# CAN_TJA1050.net
KiCad netlist of a schematic drawn in Altium Designer
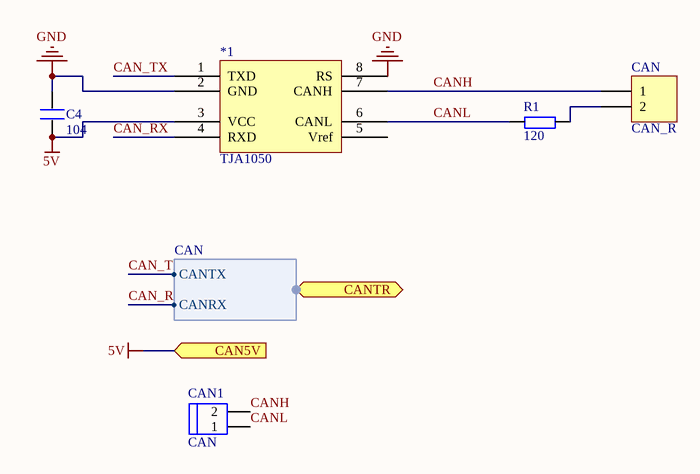
[diagram p0: CAN_TJA1050.SchDoc]

(export (version "E")
  (design (tool "Eeschema 10.0.6"))
  (components
    (comp (ref "*1") (value "TJA1050") (footprint "SOP8") (libsource (lib "TJA1050") (part "TJA1050")))
    (comp (ref "C4") (value "104") (footprint "0603P") (libsource (lib "MiniSTM32 V3.0封装库") (part "C")))
    (comp (ref "CAN")
      (value "CAN_R")
      (footprint "HDR1X2")
      (description "Header, 2-Pin")
      (fields (field (name "PUBLISHER") "Altium Limited"))
      (libsource (lib "MiniSTM32 V3.0封装库") (part "Header 2"))
    )
    (comp (ref "CAN1")
      (value "CAN")
      (footprint "HEAD2L-0.8")
      (libsource (lib "阿波罗STM32F4&F7底板封装库") (part "HEAD2"))
    )
    (comp (ref "R1") (value "120") (footprint "0603P") (libsource (lib "MiniSTM32 V3.0封装库") (part "R")))
  )
  (nets
    (net (code "2") (name "/CANH") (class "Default")
      (node (ref "*1") (pin "7") (pinfunction "CANH_7") (pintype "passive"))
      (node (ref "CAN") (pin "1") (pinfunction "1_1") (pintype "passive"))
      (node (ref "CAN1") (pin "2") (pinfunction "2_2") (pintype "passive"))
    )
    (net (code "3") (name "/CANL") (class "Default")
      (node (ref "*1") (pin "6") (pinfunction "CANL_6") (pintype "passive"))
      (node (ref "CAN1") (pin "1") (pinfunction "1_1") (pintype "passive"))
      (node (ref "R1") (pin "1") (pintype "passive"))
    )
    (net (code "4") (name "/CAN_RX") (class "Default")
      (node (ref "*1") (pin "4") (pinfunction "RXD_4") (pintype "passive"))
    )
    (net (code "5") (name "/CAN_TX") (class "Default")
      (node (ref "*1") (pin "1") (pinfunction "TXD_1") (pintype "passive"))
    )
    (net (code "7") (name "5V") (class "Default")
      (node (ref "*1") (pin "3") (pinfunction "VCC_3") (pintype "passive"))
      (node (ref "C4") (pin "1") (pintype "passive"))
    )
    (net (code "8") (name "GND") (class "Default")
      (node (ref "*1") (pin "2") (pinfunction "GND_2") (pintype "passive"))
      (node (ref "*1") (pin "8") (pinfunction "RS_8") (pintype "passive"))
      (node (ref "C4") (pin "2") (pintype "passive"))
    )
    (net (code "9") (name "Net-(CAN-Pad2)") (class "Default")
      (node (ref "CAN") (pin "2") (pinfunction "2_2") (pintype "passive"))
      (node (ref "R1") (pin "2") (pintype "passive"))
    )
    (net (code "10") (name "unconnected-(*1-Vref-Pad5)") (class "Default")
      (node (ref "*1") (pin "5") (pinfunction "Vref_5") (pintype "passive"))
    )
  )
)
